# CAN_Bridge.net
KiCad netlist of a schematic drawn in EAGLE
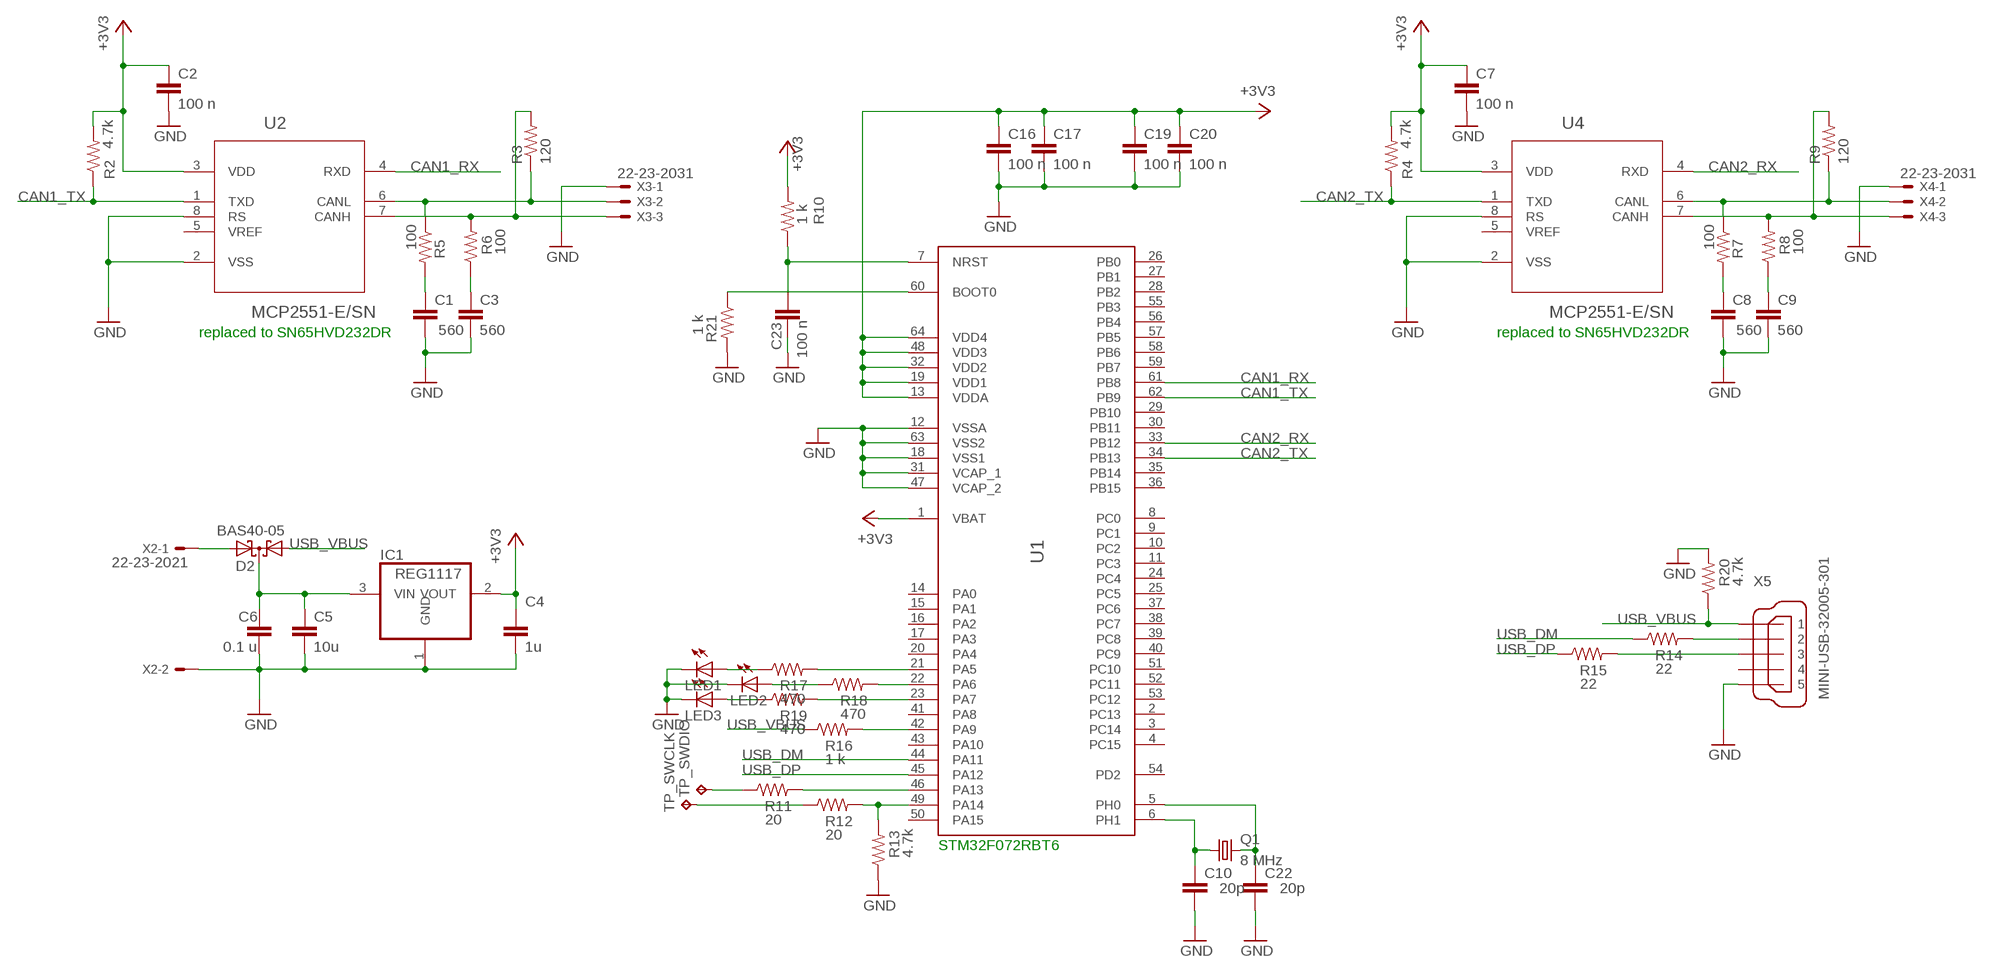
[diagram p0: schematic, sheet 1]

(export (version "E")
  (design (tool "Eeschema 10.0.6"))
  (components
    (comp (ref "C1")
      (value "560")
      (footprint "eagle-import:C0603")
      (libsource (lib "eagle-import") (part "C-EUC0603"))
    )
    (comp (ref "C2")
      (value "100 n")
      (footprint "eagle-import:C0603")
      (libsource (lib "eagle-import") (part "C-EUC0603"))
    )
    (comp (ref "C3")
      (value "560")
      (footprint "eagle-import:C0603")
      (libsource (lib "eagle-import") (part "C-EUC0603"))
    )
    (comp (ref "C4")
      (value "1u")
      (footprint "eagle-import:C0603")
      (libsource (lib "eagle-import") (part "C-EUC0603"))
    )
    (comp (ref "C5")
      (value "10u")
      (footprint "eagle-import:C1206")
      (libsource (lib "eagle-import") (part "C-EUC1206"))
    )
    (comp (ref "C6")
      (value "0.1 u")
      (footprint "eagle-import:C0603")
      (libsource (lib "eagle-import") (part "C-EUC0603"))
    )
    (comp (ref "C7")
      (value "100 n")
      (footprint "eagle-import:C0603")
      (libsource (lib "eagle-import") (part "C-EUC0603"))
    )
    (comp (ref "C8")
      (value "560")
      (footprint "eagle-import:C0603")
      (libsource (lib "eagle-import") (part "C-EUC0603"))
    )
    (comp (ref "C9")
      (value "560")
      (footprint "eagle-import:C0603")
      (libsource (lib "eagle-import") (part "C-EUC0603"))
    )
    (comp (ref "C10")
      (value "20p")
      (footprint "eagle-import:C0603")
      (libsource (lib "eagle-import") (part "C-EUC0603"))
    )
    (comp (ref "C16")
      (value "100 n")
      (footprint "eagle-import:C0603")
      (libsource (lib "eagle-import") (part "C-EUC0603"))
    )
    (comp (ref "C17")
      (value "100 n")
      (footprint "eagle-import:C0603")
      (libsource (lib "eagle-import") (part "C-EUC0603"))
    )
    (comp (ref "C19")
      (value "100 n")
      (footprint "eagle-import:C0603")
      (libsource (lib "eagle-import") (part "C-EUC0603"))
    )
    (comp (ref "C20")
      (value "100 n")
      (footprint "eagle-import:C0603")
      (libsource (lib "eagle-import") (part "C-EUC0603"))
    )
    (comp (ref "C22")
      (value "20p")
      (footprint "eagle-import:C0603")
      (libsource (lib "eagle-import") (part "C-EUC0603"))
    )
    (comp (ref "C23")
      (value "100 n")
      (footprint "eagle-import:C0603")
      (libsource (lib "eagle-import") (part "C-EUC0603"))
    )
    (comp (ref "D2")
      (value "BAS40-05")
      (footprint "eagle-import:SOT23")
      (libsource (lib "eagle-import") (part "BAS40-05"))
    )
    (comp (ref "IC1")
      (value "REG1117")
      (footprint "eagle-import:SOT223")
      (libsource (lib "eagle-import") (part "REG1117"))
    )
    (comp (ref "LED1")
      (value "LED_ESML0603")
      (footprint "eagle-import:LED_SML0603")
      (libsource (lib "eagle-import") (part "LED_ESML0603"))
    )
    (comp (ref "LED2")
      (value "LED_ESML0603")
      (footprint "eagle-import:LED_SML0603")
      (libsource (lib "eagle-import") (part "LED_ESML0603"))
    )
    (comp (ref "LED3")
      (value "LED_ESML0603")
      (footprint "eagle-import:LED_SML0603")
      (libsource (lib "eagle-import") (part "LED_ESML0603"))
    )
    (comp (ref "Q1")
      (value "8 MHz")
      (footprint "eagle-import:SM49")
      (libsource (lib "eagle-import") (part "CRYSTALSM49"))
    )
    (comp (ref "R2")
      (value "4.7k")
      (footprint "eagle-import:R0603")
      (libsource (lib "eagle-import") (part "resistor_R-US_R0603"))
    )
    (comp (ref "R3")
      (value "120")
      (footprint "eagle-import:R0805")
      (libsource (lib "eagle-import") (part "R-US_R0805"))
    )
    (comp (ref "R4")
      (value "4.7k")
      (footprint "eagle-import:R0603")
      (libsource (lib "eagle-import") (part "resistor_R-US_R0603"))
    )
    (comp (ref "R5")
      (value "100")
      (footprint "eagle-import:R0603")
      (libsource (lib "eagle-import") (part "resistor_R-US_R0603"))
    )
    (comp (ref "R6")
      (value "100")
      (footprint "eagle-import:R0603")
      (libsource (lib "eagle-import") (part "resistor_R-US_R0603"))
    )
    (comp (ref "R7")
      (value "100")
      (footprint "eagle-import:R0603")
      (libsource (lib "eagle-import") (part "resistor_R-US_R0603"))
    )
    (comp (ref "R8")
      (value "100")
      (footprint "eagle-import:R0603")
      (libsource (lib "eagle-import") (part "resistor_R-US_R0603"))
    )
    (comp (ref "R9")
      (value "120")
      (footprint "eagle-import:R0805")
      (libsource (lib "eagle-import") (part "R-US_R0805"))
    )
    (comp (ref "R10")
      (value "1 k")
      (footprint "eagle-import:R0603")
      (libsource (lib "eagle-import") (part "resistor_R-US_R0603"))
    )
    (comp (ref "R11")
      (value "20")
      (footprint "eagle-import:R0603")
      (libsource (lib "eagle-import") (part "resistor_R-US_R0603"))
    )
    (comp (ref "R12")
      (value "20")
      (footprint "eagle-import:R0603")
      (libsource (lib "eagle-import") (part "resistor_R-US_R0603"))
    )
    (comp (ref "R13")
      (value "4.7k")
      (footprint "eagle-import:R0603")
      (libsource (lib "eagle-import") (part "resistor_R-US_R0603"))
    )
    (comp (ref "R14")
      (value "22")
      (footprint "eagle-import:R0603")
      (libsource (lib "eagle-import") (part "resistor_R-US_R0603"))
    )
    (comp (ref "R15")
      (value "22")
      (footprint "eagle-import:R0603")
      (libsource (lib "eagle-import") (part "resistor_R-US_R0603"))
    )
    (comp (ref "R16")
      (value "1 k")
      (footprint "eagle-import:R0603")
      (libsource (lib "eagle-import") (part "resistor_R-US_R0603"))
    )
    (comp (ref "R17")
      (value "470")
      (footprint "eagle-import:R0603")
      (libsource (lib "eagle-import") (part "resistor_R-US_R0603"))
    )
    (comp (ref "R18")
      (value "470")
      (footprint "eagle-import:R0603")
      (libsource (lib "eagle-import") (part "resistor_R-US_R0603"))
    )
    (comp (ref "R19")
      (value "470")
      (footprint "eagle-import:R0603")
      (libsource (lib "eagle-import") (part "resistor_R-US_R0603"))
    )
    (comp (ref "R20")
      (value "4.7k")
      (footprint "eagle-import:R0603")
      (libsource (lib "eagle-import") (part "resistor_R-US_R0603"))
    )
    (comp (ref "R21")
      (value "1 k")
      (footprint "eagle-import:R0603")
      (libsource (lib "eagle-import") (part "resistor_R-US_R0603"))
    )
    (comp (ref "TP_SWCLK")
      (value "TPTP10SQ")
      (footprint "eagle-import:TP10SQ")
      (libsource (lib "eagle-import") (part "TPTP10SQ"))
    )
    (comp (ref "TP_SWDIO")
      (value "TPTP10SQ")
      (footprint "eagle-import:TP10SQ")
      (libsource (lib "eagle-import") (part "TPTP10SQ"))
    )
    (comp (ref "U1")
      (value "STM32F405XXSTM32F405XX")
      (footprint "eagle-import:LQFP64")
      (libsource (lib "eagle-import") (part "STM32F405XXSTM32F405XX"))
    )
    (comp (ref "U2")
      (value "MCP2551-E/SN")
      (footprint "eagle-import:SOIC127P600X175-8N")
      (libsource (lib "eagle-import") (part "MCP2551-E/SN"))
    )
    (comp (ref "U4")
      (value "MCP2551-E/SN")
      (footprint "eagle-import:SOIC127P600X175-8N")
      (libsource (lib "eagle-import") (part "MCP2551-E/SN"))
    )
    (comp (ref "X2")
      (value "22-23-2021")
      (footprint "eagle-import:22-23-2021")
      (fields (field (name "MF") "MOLEX"))
      (libsource (lib "eagle-import") (part "22-23-2021"))
    )
    (comp (ref "X3")
      (value "22-23-2031")
      (footprint "eagle-import:22-23-2031")
      (fields (field (name "MF") "MOLEX"))
      (libsource (lib "eagle-import") (part "22-23-2031"))
    )
    (comp (ref "X4")
      (value "22-23-2031")
      (footprint "eagle-import:22-23-2031")
      (fields (field (name "MF") "MOLEX"))
      (libsource (lib "eagle-import") (part "22-23-2031"))
    )
    (comp (ref "X5")
      (value "MINI-USB-32005-301")
      (footprint "eagle-import:32005-301")
      (libsource (lib "eagle-import") (part "MINI-USB-32005-301"))
    )
  )
  (nets
    (net (code "1") (name "+3V3") (class "Default")
      (node (ref "C16") (pin "1") (pinfunction "1_1") (pintype "passive"))
      (node (ref "C17") (pin "1") (pinfunction "1_1") (pintype "passive"))
      (node (ref "C19") (pin "1") (pinfunction "1_1") (pintype "passive"))
      (node (ref "C2") (pin "1") (pinfunction "1_1") (pintype "passive"))
      (node (ref "C20") (pin "1") (pinfunction "1_1") (pintype "passive"))
      (node (ref "C4") (pin "1") (pinfunction "1_1") (pintype "passive"))
      (node (ref "C7") (pin "1") (pinfunction "1_1") (pintype "passive"))
      (node (ref "IC1") (pin "2") (pinfunction "VOUT_2") (pintype "output"))
      (node (ref "R10") (pin "2") (pinfunction "2_2") (pintype "passive"))
      (node (ref "R2") (pin "2") (pinfunction "2_2") (pintype "passive"))
      (node (ref "R4") (pin "2") (pinfunction "2_2") (pintype "passive"))
      (node (ref "U1") (pin "1") (pinfunction "VBAT_1") (pintype "power_in"))
      (node (ref "U1") (pin "13") (pinfunction "VDDA_13") (pintype "power_in"))
      (node (ref "U1") (pin "19") (pinfunction "VDD1_19") (pintype "power_in"))
      (node (ref "U1") (pin "32") (pinfunction "VDD2_32") (pintype "power_in"))
      (node (ref "U1") (pin "48") (pinfunction "VDD3_48") (pintype "power_in"))
      (node (ref "U1") (pin "64") (pinfunction "VDD4_64") (pintype "power_in"))
      (node (ref "U2") (pin "3") (pinfunction "VDD_3") (pintype "power_in"))
      (node (ref "U4") (pin "3") (pinfunction "VDD_3") (pintype "power_in"))
    )
    (net (code "2") (name "/CAN1_RX") (class "Default")
      (node (ref "U1") (pin "61") (pinfunction "PB8_61") (pintype "bidirectional"))
      (node (ref "U2") (pin "4") (pinfunction "RXD_4") (pintype "output"))
    )
    (net (code "3") (name "/CAN1_TX") (class "Default")
      (node (ref "R2") (pin "1") (pinfunction "1_1") (pintype "passive"))
      (node (ref "U1") (pin "62") (pinfunction "PB9_62") (pintype "bidirectional"))
      (node (ref "U2") (pin "1") (pinfunction "TXD_1") (pintype "input"))
    )
    (net (code "4") (name "/CAN2_RX") (class "Default")
      (node (ref "U1") (pin "33") (pinfunction "PB12_33") (pintype "bidirectional"))
      (node (ref "U4") (pin "4") (pinfunction "RXD_4") (pintype "output"))
    )
    (net (code "5") (name "/CAN2_TX") (class "Default")
      (node (ref "R4") (pin "1") (pinfunction "1_1") (pintype "passive"))
      (node (ref "U1") (pin "34") (pinfunction "PB13_34") (pintype "bidirectional"))
      (node (ref "U4") (pin "1") (pinfunction "TXD_1") (pintype "input"))
    )
    (net (code "6") (name "/USB_DM") (class "Default")
      (node (ref "R14") (pin "1") (pinfunction "1_1") (pintype "passive"))
      (node (ref "U1") (pin "44") (pinfunction "PA11_44") (pintype "bidirectional"))
    )
    (net (code "7") (name "/USB_DP") (class "Default")
      (node (ref "R15") (pin "1") (pinfunction "1_1") (pintype "passive"))
      (node (ref "U1") (pin "45") (pinfunction "PA12_45") (pintype "bidirectional"))
    )
    (net (code "8") (name "/USB_VBUS") (class "Default")
      (node (ref "D2") (pin "1") (pinfunction "A1_1") (pintype "passive"))
      (node (ref "R16") (pin "1") (pinfunction "1_1") (pintype "passive"))
      (node (ref "R20") (pin "1") (pinfunction "1_1") (pintype "passive"))
      (node (ref "X5") (pin "1") (pinfunction "1_1") (pintype "passive"))
    )
    (net (code "9") (name "GND") (class "Default")
      (node (ref "C1") (pin "2") (pinfunction "2_2") (pintype "passive"))
      (node (ref "C10") (pin "2") (pinfunction "2_2") (pintype "passive"))
      (node (ref "C16") (pin "2") (pinfunction "2_2") (pintype "passive"))
      (node (ref "C17") (pin "2") (pinfunction "2_2") (pintype "passive"))
      (node (ref "C19") (pin "2") (pinfunction "2_2") (pintype "passive"))
      (node (ref "C2") (pin "2") (pinfunction "2_2") (pintype "passive"))
      (node (ref "C20") (pin "2") (pinfunction "2_2") (pintype "passive"))
      (node (ref "C22") (pin "2") (pinfunction "2_2") (pintype "passive"))
      (node (ref "C23") (pin "2") (pinfunction "2_2") (pintype "passive"))
      (node (ref "C3") (pin "2") (pinfunction "2_2") (pintype "passive"))
      (node (ref "C4") (pin "2") (pinfunction "2_2") (pintype "passive"))
      (node (ref "C5") (pin "2") (pinfunction "2_2") (pintype "passive"))
      (node (ref "C6") (pin "2") (pinfunction "2_2") (pintype "passive"))
      (node (ref "C7") (pin "2") (pinfunction "2_2") (pintype "passive"))
      (node (ref "C8") (pin "2") (pinfunction "2_2") (pintype "passive"))
      (node (ref "C9") (pin "2") (pinfunction "2_2") (pintype "passive"))
      (node (ref "IC1") (pin "1") (pinfunction "GND_1") (pintype "power_in"))
      (node (ref "LED1") (pin "C") (pinfunction "C_C") (pintype "passive"))
      (node (ref "LED2") (pin "C") (pinfunction "C_C") (pintype "passive"))
      (node (ref "LED3") (pin "C") (pinfunction "C_C") (pintype "passive"))
      (node (ref "R13") (pin "1") (pinfunction "1_1") (pintype "passive"))
      (node (ref "R20") (pin "2") (pinfunction "2_2") (pintype "passive"))
      (node (ref "R21") (pin "2") (pinfunction "2_2") (pintype "passive"))
      (node (ref "U1") (pin "12") (pinfunction "VSSA_12") (pintype "power_in"))
      (node (ref "U1") (pin "18") (pinfunction "VSS1_18") (pintype "power_in"))
      (node (ref "U1") (pin "31") (pinfunction "VCAP_1_31") (pintype "power_in"))
      (node (ref "U1") (pin "47") (pinfunction "VCAP_2_47") (pintype "power_in"))
      (node (ref "U1") (pin "63") (pinfunction "VSS2_63") (pintype "power_in"))
      (node (ref "U2") (pin "2") (pinfunction "VSS_2") (pintype "power_in"))
      (node (ref "U2") (pin "8") (pinfunction "RS_8") (pintype "input"))
      (node (ref "U4") (pin "2") (pinfunction "VSS_2") (pintype "power_in"))
      (node (ref "U4") (pin "8") (pinfunction "RS_8") (pintype "input"))
      (node (ref "X2") (pin "2") (pinfunction "S_2") (pintype "passive"))
      (node (ref "X3") (pin "1") (pinfunction "S_1") (pintype "passive"))
      (node (ref "X4") (pin "1") (pinfunction "S_1") (pintype "passive"))
      (node (ref "X5") (pin "5") (pinfunction "5_5") (pintype "passive"))
    )
    (net (code "10") (name "Net-(C1-Pad1)") (class "Default")
      (node (ref "C1") (pin "1") (pinfunction "1_1") (pintype "passive"))
      (node (ref "R5") (pin "2") (pinfunction "2_2") (pintype "passive"))
    )
    (net (code "11") (name "Net-(C3-Pad1)") (class "Default")
      (node (ref "C3") (pin "1") (pinfunction "1_1") (pintype "passive"))
      (node (ref "R6") (pin "1") (pinfunction "1_1") (pintype "passive"))
    )
    (net (code "12") (name "Net-(C8-Pad1)") (class "Default")
      (node (ref "C8") (pin "1") (pinfunction "1_1") (pintype "passive"))
      (node (ref "R7") (pin "2") (pinfunction "2_2") (pintype "passive"))
    )
    (net (code "13") (name "Net-(C9-Pad1)") (class "Default")
      (node (ref "C9") (pin "1") (pinfunction "1_1") (pintype "passive"))
      (node (ref "R8") (pin "1") (pinfunction "1_1") (pintype "passive"))
    )
    (net (code "14") (name "Net-(D2-A2)") (class "Default")
      (node (ref "D2") (pin "2") (pinfunction "A2_2") (pintype "passive"))
      (node (ref "X2") (pin "1") (pinfunction "S_1") (pintype "passive"))
    )
    (net (code "15") (name "Net-(D2-C)") (class "Default")
      (node (ref "C5") (pin "1") (pinfunction "1_1") (pintype "passive"))
      (node (ref "C6") (pin "1") (pinfunction "1_1") (pintype "passive"))
      (node (ref "D2") (pin "3") (pinfunction "C_3") (pintype "passive"))
      (node (ref "IC1") (pin "3") (pinfunction "VIN_3") (pintype "input"))
    )
    (net (code "16") (name "Net-(LED1-PadA)") (class "Default")
      (node (ref "LED1") (pin "A") (pinfunction "A_A") (pintype "passive"))
      (node (ref "R17") (pin "1") (pinfunction "1_1") (pintype "passive"))
    )
    (net (code "17") (name "Net-(LED2-PadA)") (class "Default")
      (node (ref "LED2") (pin "A") (pinfunction "A_A") (pintype "passive"))
      (node (ref "R18") (pin "1") (pinfunction "1_1") (pintype "passive"))
    )
    (net (code "18") (name "Net-(LED3-PadA)") (class "Default")
      (node (ref "LED3") (pin "A") (pinfunction "A_A") (pintype "passive"))
      (node (ref "R19") (pin "1") (pinfunction "1_1") (pintype "passive"))
    )
    (net (code "19") (name "Net-(R11-Pad1)") (class "Default")
      (node (ref "R11") (pin "1") (pinfunction "1_1") (pintype "passive"))
      (node (ref "TP_SWDIO") (pin "TP") (pinfunction "TP_TP") (pintype "input"))
    )
    (net (code "20") (name "Net-(R12-Pad1)") (class "Default")
      (node (ref "R12") (pin "1") (pinfunction "1_1") (pintype "passive"))
      (node (ref "TP_SWCLK") (pin "TP") (pinfunction "TP_TP") (pintype "input"))
    )
    (net (code "21") (name "Net-(R14-Pad2)") (class "Default")
      (node (ref "R14") (pin "2") (pinfunction "2_2") (pintype "passive"))
      (node (ref "X5") (pin "2") (pinfunction "2_2") (pintype "passive"))
    )
    (net (code "22") (name "Net-(R15-Pad2)") (class "Default")
      (node (ref "R15") (pin "2") (pinfunction "2_2") (pintype "passive"))
      (node (ref "X5") (pin "3") (pinfunction "3_3") (pintype "passive"))
    )
    (net (code "23") (name "Net-(U1-BOOT0)") (class "Default")
      (node (ref "R21") (pin "1") (pinfunction "1_1") (pintype "passive"))
      (node (ref "U1") (pin "60") (pinfunction "BOOT0_60") (pintype "bidirectional"))
    )
    (net (code "24") (name "Net-(U1-NRST)") (class "Default")
      (node (ref "C23") (pin "1") (pinfunction "1_1") (pintype "passive"))
      (node (ref "R10") (pin "1") (pinfunction "1_1") (pintype "passive"))
      (node (ref "U1") (pin "7") (pinfunction "NRST_7") (pintype "bidirectional"))
    )
    (net (code "25") (name "Net-(U1-PA5)") (class "Default")
      (node (ref "R17") (pin "2") (pinfunction "2_2") (pintype "passive"))
      (node (ref "U1") (pin "21") (pinfunction "PA5_21") (pintype "bidirectional"))
    )
    (net (code "26") (name "Net-(U1-PA6)") (class "Default")
      (node (ref "R18") (pin "2") (pinfunction "2_2") (pintype "passive"))
      (node (ref "U1") (pin "22") (pinfunction "PA6_22") (pintype "bidirectional"))
    )
    (net (code "27") (name "Net-(U1-PA7)") (class "Default")
      (node (ref "R19") (pin "2") (pinfunction "2_2") (pintype "passive"))
      (node (ref "U1") (pin "23") (pinfunction "PA7_23") (pintype "bidirectional"))
    )
    (net (code "28") (name "Net-(U1-PA9)") (class "Default")
      (node (ref "R16") (pin "2") (pinfunction "2_2") (pintype "passive"))
      (node (ref "U1") (pin "42") (pinfunction "PA9_42") (pintype "bidirectional"))
    )
    (net (code "29") (name "Net-(U1-PA13)") (class "Default")
      (node (ref "R11") (pin "2") (pinfunction "2_2") (pintype "passive"))
      (node (ref "U1") (pin "46") (pinfunction "PA13_46") (pintype "bidirectional"))
    )
    (net (code "30") (name "Net-(U1-PA14)") (class "Default")
      (node (ref "R12") (pin "2") (pinfunction "2_2") (pintype "passive"))
      (node (ref "R13") (pin "2") (pinfunction "2_2") (pintype "passive"))
      (node (ref "U1") (pin "49") (pinfunction "PA14_49") (pintype "bidirectional"))
    )
    (net (code "31") (name "Net-(U1-PH0)") (class "Default")
      (node (ref "C22") (pin "1") (pinfunction "1_1") (pintype "passive"))
      (node (ref "Q1") (pin "2") (pinfunction "2_2") (pintype "passive"))
      (node (ref "U1") (pin "5") (pinfunction "PH0_5") (pintype "bidirectional"))
    )
    (net (code "32") (name "Net-(U1-PH1)") (class "Default")
      (node (ref "C10") (pin "1") (pinfunction "1_1") (pintype "passive"))
      (node (ref "Q1") (pin "1") (pinfunction "1_1") (pintype "passive"))
      (node (ref "U1") (pin "6") (pinfunction "PH1_6") (pintype "bidirectional"))
    )
    (net (code "33") (name "Net-(U2-CANH)") (class "Default")
      (node (ref "R3") (pin "2") (pinfunction "2_2") (pintype "passive"))
      (node (ref "R6") (pin "2") (pinfunction "2_2") (pintype "passive"))
      (node (ref "U2") (pin "7") (pinfunction "CANH_7") (pintype "output"))
      (node (ref "X3") (pin "3") (pinfunction "S_3") (pintype "passive"))
    )
    (net (code "34") (name "Net-(U2-CANL)") (class "Default")
      (node (ref "R3") (pin "1") (pinfunction "1_1") (pintype "passive"))
      (node (ref "R5") (pin "1") (pinfunction "1_1") (pintype "passive"))
      (node (ref "U2") (pin "6") (pinfunction "CANL_6") (pintype "output"))
      (node (ref "X3") (pin "2") (pinfunction "S_2") (pintype "passive"))
    )
    (net (code "35") (name "Net-(U4-CANH)") (class "Default")
      (node (ref "R8") (pin "2") (pinfunction "2_2") (pintype "passive"))
      (node (ref "R9") (pin "2") (pinfunction "2_2") (pintype "passive"))
      (node (ref "U4") (pin "7") (pinfunction "CANH_7") (pintype "output"))
      (node (ref "X4") (pin "3") (pinfunction "S_3") (pintype "passive"))
    )
    (net (code "36") (name "Net-(U4-CANL)") (class "Default")
      (node (ref "R7") (pin "1") (pinfunction "1_1") (pintype "passive"))
      (node (ref "R9") (pin "1") (pinfunction "1_1") (pintype "passive"))
      (node (ref "U4") (pin "6") (pinfunction "CANL_6") (pintype "output"))
      (node (ref "X4") (pin "2") (pinfunction "S_2") (pintype "passive"))
    )
    (net (code "37") (name "unconnected-(U1-PA0-Pad14)") (class "Default")
      (node (ref "U1") (pin "14") (pinfunction "PA0_14") (pintype "bidirectional"))
    )
    (net (code "38") (name "unconnected-(U1-PA1-Pad15)") (class "Default")
      (node (ref "U1") (pin "15") (pinfunction "PA1_15") (pintype "bidirectional"))
    )
    (net (code "39") (name "unconnected-(U1-PA2-Pad16)") (class "Default")
      (node (ref "U1") (pin "16") (pinfunction "PA2_16") (pintype "bidirectional"))
    )
    (net (code "40") (name "unconnected-(U1-PA3-Pad17)") (class "Default")
      (node (ref "U1") (pin "17") (pinfunction "PA3_17") (pintype "bidirectional"))
    )
    (net (code "41") (name "unconnected-(U1-PA4-Pad20)") (class "Default")
      (node (ref "U1") (pin "20") (pinfunction "PA4_20") (pintype "bidirectional"))
    )
    (net (code "42") (name "unconnected-(U1-PA8-Pad41)") (class "Default")
      (node (ref "U1") (pin "41") (pinfunction "PA8_41") (pintype "bidirectional"))
    )
    (net (code "43") (name "unconnected-(U1-PA10-Pad43)") (class "Default")
      (node (ref "U1") (pin "43") (pinfunction "PA10_43") (pintype "bidirectional"))
    )
    (net (code "44") (name "unconnected-(U1-PA15-Pad50)") (class "Default")
      (node (ref "U1") (pin "50") (pinfunction "PA15_50") (pintype "bidirectional"))
    )
    (net (code "45") (name "unconnected-(U1-PB0-Pad26)") (class "Default")
      (node (ref "U1") (pin "26") (pinfunction "PB0_26") (pintype "bidirectional"))
    )
    (net (code "46") (name "unconnected-(U1-PB1-Pad27)") (class "Default")
      (node (ref "U1") (pin "27") (pinfunction "PB1_27") (pintype "bidirectional"))
    )
    (net (code "47") (name "unconnected-(U1-PB2-Pad28)") (class "Default")
      (node (ref "U1") (pin "28") (pinfunction "PB2_28") (pintype "bidirectional"))
    )
    (net (code "48") (name "unconnected-(U1-PB3-Pad55)") (class "Default")
      (node (ref "U1") (pin "55") (pinfunction "PB3_55") (pintype "bidirectional"))
    )
    (net (code "49") (name "unconnected-(U1-PB4-Pad56)") (class "Default")
      (node (ref "U1") (pin "56") (pinfunction "PB4_56") (pintype "bidirectional"))
    )
    (net (code "50") (name "unconnected-(U1-PB5-Pad57)") (class "Default")
      (node (ref "U1") (pin "57") (pinfunction "PB5_57") (pintype "bidirectional"))
    )
    (net (code "51") (name "unconnected-(U1-PB6-Pad58)") (class "Default")
      (node (ref "U1") (pin "58") (pinfunction "PB6_58") (pintype "bidirectional"))
    )
    (net (code "52") (name "unconnected-(U1-PB7-Pad59)") (class "Default")
      (node (ref "U1") (pin "59") (pinfunction "PB7_59") (pintype "bidirectional"))
    )
    (net (code "53") (name "unconnected-(U1-PB10-Pad29)") (class "Default")
      (node (ref "U1") (pin "29") (pinfunction "PB10_29") (pintype "bidirectional"))
    )
    (net (code "54") (name "unconnected-(U1-PB11-Pad30)") (class "Default")
      (node (ref "U1") (pin "30") (pinfunction "PB11_30") (pintype "bidirectional"))
    )
    (net (code "55") (name "unconnected-(U1-PB14-Pad35)") (class "Default")
      (node (ref "U1") (pin "35") (pinfunction "PB14_35") (pintype "bidirectional"))
    )
    (net (code "56") (name "unconnected-(U1-PB15-Pad36)") (class "Default")
      (node (ref "U1") (pin "36") (pinfunction "PB15_36") (pintype "bidirectional"))
    )
    (net (code "57") (name "unconnected-(U1-PC0-Pad8)") (class "Default")
      (node (ref "U1") (pin "8") (pinfunction "PC0_8") (pintype "bidirectional"))
    )
    (net (code "58") (name "unconnected-(U1-PC1-Pad9)") (class "Default")
      (node (ref "U1") (pin "9") (pinfunction "PC1_9") (pintype "bidirectional"))
    )
    (net (code "59") (name "unconnected-(U1-PC2-Pad10)") (class "Default")
      (node (ref "U1") (pin "10") (pinfunction "PC2_10") (pintype "bidirectional"))
    )
    (net (code "60") (name "unconnected-(U1-PC3-Pad11)") (class "Default")
      (node (ref "U1") (pin "11") (pinfunction "PC3_11") (pintype "bidirectional"))
    )
    (net (code "61") (name "unconnected-(U1-PC4-Pad24)") (class "Default")
      (node (ref "U1") (pin "24") (pinfunction "PC4_24") (pintype "bidirectional"))
    )
    (net (code "62") (name "unconnected-(U1-PC5-Pad25)") (class "Default")
      (node (ref "U1") (pin "25") (pinfunction "PC5_25") (pintype "bidirectional"))
    )
    (net (code "63") (name "unconnected-(U1-PC6-Pad37)") (class "Default")
      (node (ref "U1") (pin "37") (pinfunction "PC6_37") (pintype "bidirectional"))
    )
    (net (code "64") (name "unconnected-(U1-PC7-Pad38)") (class "Default")
      (node (ref "U1") (pin "38") (pinfunction "PC7_38") (pintype "bidirectional"))
    )
    (net (code "65") (name "unconnected-(U1-PC8-Pad39)") (class "Default")
      (node (ref "U1") (pin "39") (pinfunction "PC8_39") (pintype "bidirectional"))
    )
    (net (code "66") (name "unconnected-(U1-PC9-Pad40)") (class "Default")
      (node (ref "U1") (pin "40") (pinfunction "PC9_40") (pintype "bidirectional"))
    )
    (net (code "67") (name "unconnected-(U1-PC10-Pad51)") (class "Default")
      (node (ref "U1") (pin "51") (pinfunction "PC10_51") (pintype "bidirectional"))
    )
    (net (code "68") (name "unconnected-(U1-PC11-Pad52)") (class "Default")
      (node (ref "U1") (pin "52") (pinfunction "PC11_52") (pintype "bidirectional"))
    )
    (net (code "69") (name "unconnected-(U1-PC12-Pad53)") (class "Default")
      (node (ref "U1") (pin "53") (pinfunction "PC12_53") (pintype "bidirectional"))
    )
    (net (code "70") (name "unconnected-(U1-PC13-Pad2)") (class "Default")
      (node (ref "U1") (pin "2") (pinfunction "PC13_2") (pintype "bidirectional"))
    )
    (net (code "71") (name "unconnected-(U1-PC14-Pad3)") (class "Default")
      (node (ref "U1") (pin "3") (pinfunction "PC14_3") (pintype "bidirectional"))
    )
    (net (code "72") (name "unconnected-(U1-PC15-Pad4)") (class "Default")
      (node (ref "U1") (pin "4") (pinfunction "PC15_4") (pintype "bidirectional"))
    )
    (net (code "73") (name "unconnected-(U1-PD2-Pad54)") (class "Default")
      (node (ref "U1") (pin "54") (pinfunction "PD2_54") (pintype "bidirectional"))
    )
    (net (code "74") (name "unconnected-(U2-VREF-Pad5)") (class "Default")
      (node (ref "U2") (pin "5") (pinfunction "VREF_5") (pintype "input"))
    )
    (net (code "75") (name "unconnected-(U4-VREF-Pad5)") (class "Default")
      (node (ref "U4") (pin "5") (pinfunction "VREF_5") (pintype "input"))
    )
    (net (code "76") (name "unconnected-(X5-Pad4)") (class "Default")
      (node (ref "X5") (pin "4") (pinfunction "4_4") (pintype "passive"))
    )
  )
)
